# Power.net
KiCad netlist of a schematic drawn in Altium Designer
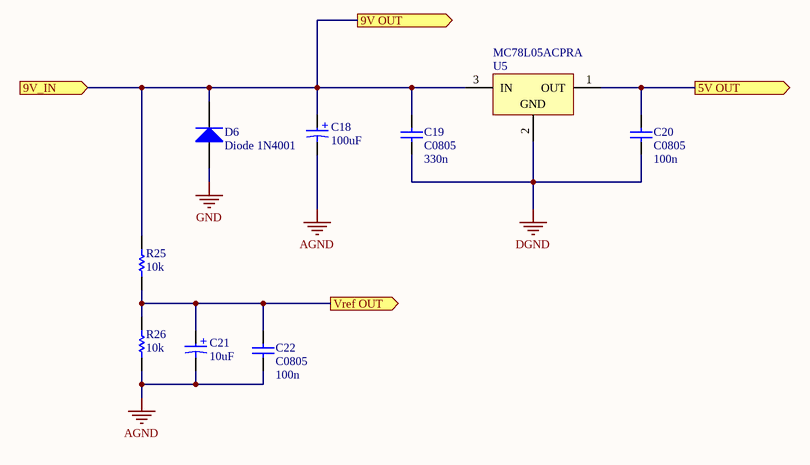
[diagram p0: Power.SchDoc]

(export (version "E")
  (design (tool "Eeschema 10.0.6"))
  (components
    (comp (ref "C18")
      (value "100uF")
      (footprint "100uF CAP 2.5mm")
      (fields
        (field (name "MPN") "UFW1E101MED1TD")
        (field (name "MANUFACTURER") "Nichicon")
        (field (name "Comment") "CAP ELEC 100uF")
      )
      (libsource (lib "Parts") (part "CAP ELEC 100uF"))
    )
    (comp (ref "C19")
      (value "C0805")
      (footprint "0805")
      (description "Ceramic Chip Capacitor - Standard")
      (fields (field (name "ALTIUM_VALUE") "330n") (field (name "PUBLISHER") "Altium Limited"))
      (libsource (lib "KEMET Chip Capacitor") (part "C0805"))
    )
    (comp (ref "C20")
      (value "C0805")
      (footprint "0805")
      (description "Ceramic Chip Capacitor - Standard")
      (fields (field (name "ALTIUM_VALUE") "100n") (field (name "PUBLISHER") "Altium Limited"))
      (libsource (lib "KEMET Chip Capacitor") (part "C0805"))
    )
    (comp (ref "C21")
      (value "10uF")
      (footprint "CAP 10uF")
      (fields
        (field (name "MPN") "USR1E100MDD1TE")
        (field (name "MANUFACTURER") "Nichicon")
        (field (name "Comment") "CAP ELEC 10uF")
      )
      (libsource (lib "Parts") (part "CAP ELEC 10uF"))
    )
    (comp (ref "C22")
      (value "C0805")
      (footprint "0805")
      (description "Ceramic Chip Capacitor - Standard")
      (fields (field (name "ALTIUM_VALUE") "100n") (field (name "PUBLISHER") "Altium Limited"))
      (libsource (lib "KEMET Chip Capacitor") (part "C0805"))
    )
    (comp (ref "D6")
      (value "Diode 1N4001")
      (footprint "DO-41")
      (description "1 Amp General Purpose Rectifier")
      (fields (field (name "PUBLISHER") "Altium Limited"))
      (libsource (lib "Miscellaneous Devices") (part "Diode 1N4001"))
    )
    (comp (ref "R25")
      (value "10k")
      (footprint "ERA-0805")
      (fields (field (name "PUBLISHER") "Altium Limited"))
      (libsource (lib "Panasonic Resistor") (part "ERAS"))
    )
    (comp (ref "R26")
      (value "10k")
      (footprint "ERA-0805")
      (fields (field (name "PUBLISHER") "Altium Limited"))
      (libsource (lib "Panasonic Resistor") (part "ERAS"))
    )
    (comp (ref "U5")
      (value "MC78L05ACPRA")
      (footprint "29-04")
      (description "Three-Terminal Low Current Positive Voltage Regulator")
      (fields (field (name "PUBLISHER") "Altium Limited"))
      (libsource (lib "ON Semi Power Mgt Voltage Regulator") (part "MC78L05ACPRA"))
    )
  )
  (nets
    (net (code "1") (name "/5V OUT") (class "Default")
      (node (ref "C20") (pin "2") (pinfunction "2_2") (pintype "passive"))
      (node (ref "U5") (pin "1") (pinfunction "OUT_1") (pintype "power_in"))
    )
    (net (code "2") (name "/9V OUT") (class "Default")
      (node (ref "C18") (pin "1") (pinfunction "1_1") (pintype "passive"))
      (node (ref "C19") (pin "2") (pinfunction "2_2") (pintype "passive"))
      (node (ref "D6") (pin "2") (pinfunction "K_2") (pintype "passive"))
      (node (ref "R25") (pin "2") (pinfunction "2_2") (pintype "passive"))
      (node (ref "U5") (pin "3") (pinfunction "IN_3") (pintype "power_in"))
    )
    (net (code "3") (name "/Vref OUT") (class "Default")
      (node (ref "C21") (pin "1") (pinfunction "1_1") (pintype "passive"))
      (node (ref "C22") (pin "2") (pinfunction "2_2") (pintype "passive"))
      (node (ref "R25") (pin "1") (pinfunction "1_1") (pintype "passive"))
      (node (ref "R26") (pin "2") (pinfunction "2_2") (pintype "passive"))
    )
    (net (code "4") (name "AGND") (class "Default")
      (node (ref "C18") (pin "2") (pinfunction "2_2") (pintype "passive"))
      (node (ref "C21") (pin "2") (pinfunction "2_2") (pintype "passive"))
      (node (ref "C22") (pin "1") (pinfunction "1_1") (pintype "passive"))
      (node (ref "R26") (pin "1") (pinfunction "1_1") (pintype "passive"))
    )
    (net (code "5") (name "DGND") (class "Default")
      (node (ref "C19") (pin "1") (pinfunction "1_1") (pintype "passive"))
      (node (ref "C20") (pin "1") (pinfunction "1_1") (pintype "passive"))
      (node (ref "U5") (pin "2") (pinfunction "GND_2") (pintype "power_in"))
    )
    (net (code "6") (name "GND") (class "Default")
      (node (ref "D6") (pin "1") (pinfunction "A_1") (pintype "passive"))
    )
  )
)
